# controlled_rectifier.net
KiCad netlist of a schematic drawn in Altium Designer
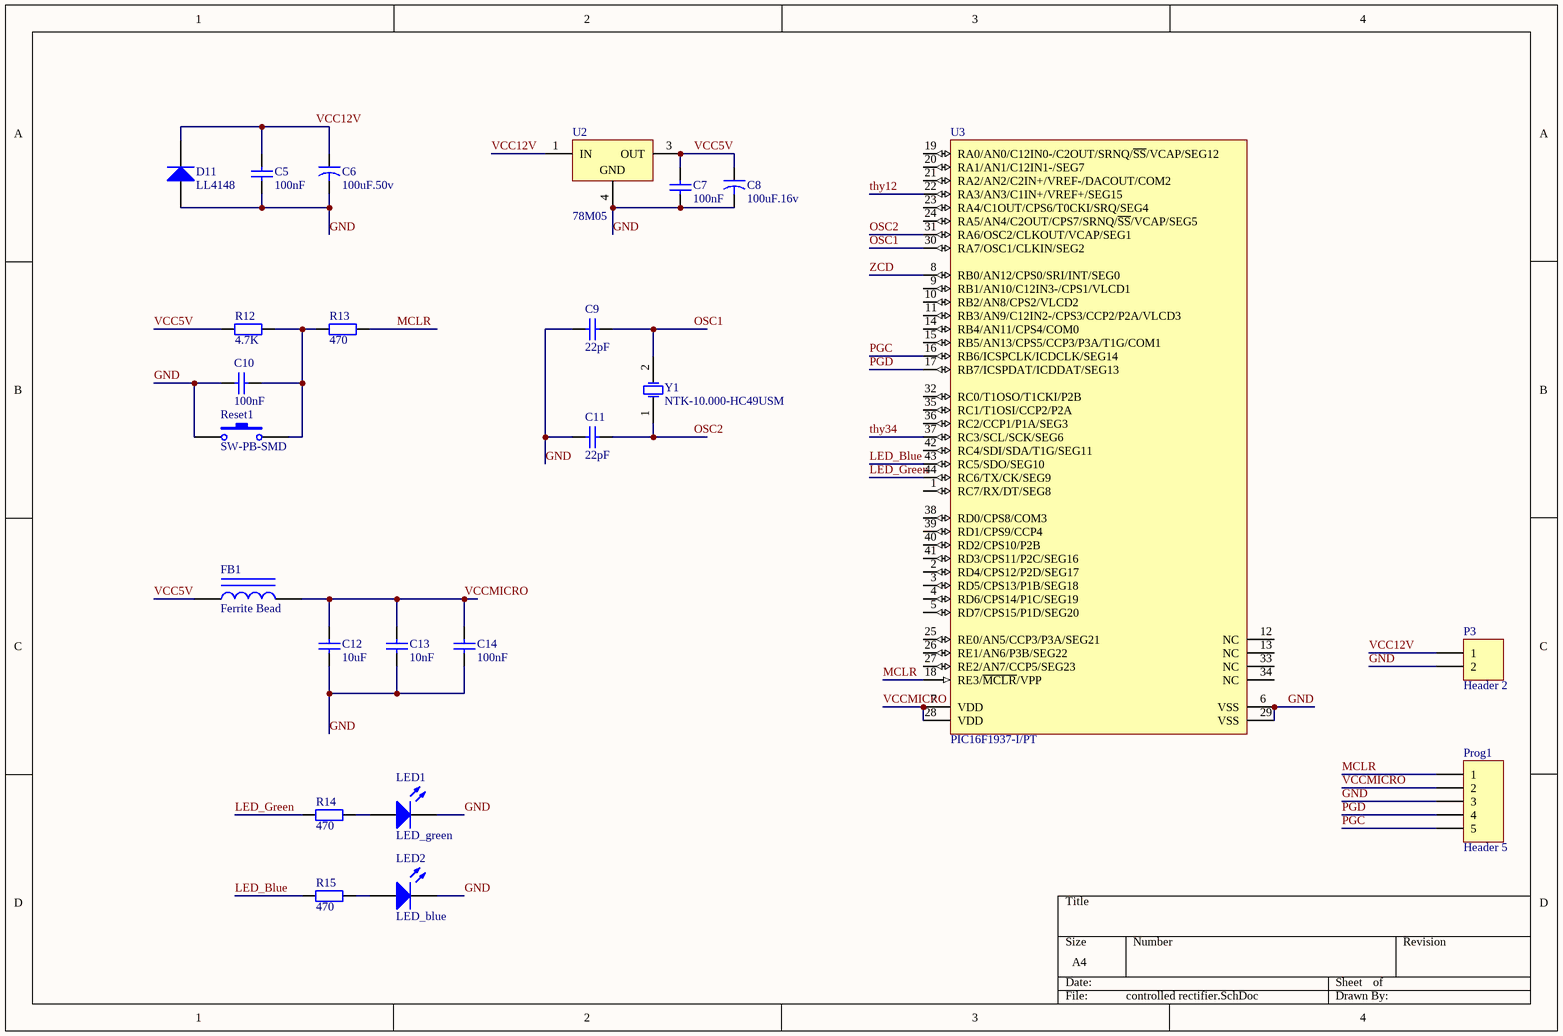
[diagram p0: controlled rectifier.SchDoc]

(export (version "E")
  (design (tool "Eeschema 10.0.6"))
  (components
    (comp (ref "C5")
      (value "100nF")
      (footprint "CAPS_0805")
      (description "CAP 0805")
      (fields (field (name "DESIGNER") "Abbas Basereh"))
      (libsource (lib "2016AbbasBasereh9365731239-12-10-95_-275613969") (part "CAP SMD 0805"))
    )
    (comp (ref "C6")
      (value "100uF.50v")
      (footprint "CAP_ELEC_SIZE_G")
      (description "Capacitor")
      (fields (field (name "PUBLISHER") "Altium Limited"))
      (libsource (lib "Miscellaneous Devices") (part "Cap2"))
    )
    (comp (ref "C7")
      (value "100nF")
      (footprint "CAPS_0805")
      (description "CAP 0805")
      (fields (field (name "DESIGNER") "Abbas Basereh"))
      (libsource (lib "2016AbbasBasereh9365731239-12-10-95_-275613969") (part "CAP SMD 0805"))
    )
    (comp (ref "C8")
      (value "100uF.16v")
      (footprint "CAP_ELEC_6.3x4.2")
      (description "Capacitor")
      (fields (field (name "PUBLISHER") "Altium Limited"))
      (libsource (lib "Miscellaneous Devices") (part "Cap2"))
    )
    (comp (ref "C9")
      (value "22pF")
      (footprint "CAPS_0805")
      (description "Capacitor")
      (fields (field (name "PUBLISHER") "Altium Limited"))
      (libsource (lib "DCMB_Economy_V00") (part "Cap"))
    )
    (comp (ref "C10")
      (value "100nF")
      (footprint "CAPS_0805")
      (description "Capacitor")
      (fields (field (name "PUBLISHER") "Altium Limited"))
      (libsource (lib "Miscellaneous Devices") (part "Cap"))
    )
    (comp (ref "C11")
      (value "22pF")
      (footprint "CAPS_0805")
      (description "Capacitor")
      (fields (field (name "PUBLISHER") "Altium Limited"))
      (libsource (lib "DCMB_Economy_V00") (part "Cap"))
    )
    (comp (ref "C12")
      (value "10uF")
      (footprint "CAPS_0805")
      (description "Capacitor")
      (fields (field (name "PUBLISHER") "Altium Limited"))
      (libsource (lib "DCMB_Economy_V00") (part "Cap"))
    )
    (comp (ref "C13")
      (value "10nF")
      (footprint "CAPS_0805")
      (description "Capacitor")
      (fields (field (name "PUBLISHER") "Altium Limited"))
      (libsource (lib "DCMB_Economy_V00") (part "Cap"))
    )
    (comp (ref "C14")
      (value "100nF")
      (footprint "CAPS_0805")
      (description "Capacitor")
      (fields (field (name "PUBLISHER") "Altium Limited"))
      (libsource (lib "DCMB_Economy_V00") (part "Cap"))
    )
    (comp (ref "D11")
      (value "LL4148")
      (footprint "SOD80, LL-34")
      (description "Default Diode")
      (fields (field (name "PUBLISHER") "Altium Limited"))
      (libsource (lib "Miscellaneous Devices") (part "Diode"))
    )
    (comp (ref "FB1")
      (value "Ferrite Bead")
      (footprint "FBC2012N")
      (description "Magnetic-Core Inductor")
      (fields (field (name "PUBLISHER") "Altium Limited"))
      (libsource (lib "Miscellaneous Devices") (part "Inductor Iron"))
    )
    (comp (ref "LED1")
      (value "LED_green")
      (footprint "LED-0805-A")
      (description "Typical RED, GREEN, YELLOW, AMBER GaAs LED")
      (fields (field (name "PUBLISHER") "Altium Limited"))
      (libsource (lib "Miscellaneous Devices") (part "LED2"))
    )
    (comp (ref "LED2")
      (value "LED_blue")
      (footprint "LED-0805-A")
      (description "Typical RED, GREEN, YELLOW, AMBER GaAs LED")
      (fields (field (name "PUBLISHER") "Altium Limited"))
      (libsource (lib "Miscellaneous Devices") (part "LED2"))
    )
    (comp (ref "P3")
      (value "Header 2")
      (footprint "Phoenix 2 Pin -RA")
      (description "Header, 2-Pin")
      (fields (field (name "PUBLISHER") "Altium Limited"))
      (libsource (lib "Miscellaneous Connectors") (part "Header 2"))
    )
    (comp (ref "Prog1")
      (value "Header 5")
      (footprint "SH-5 Pin")
      (description "Header, 5-Pin")
      (fields (field (name "PUBLISHER") "Altium Limited"))
      (libsource (lib "Miscellaneous Connectors") (part "Header 5"))
    )
    (comp (ref "R12")
      (value "4.7K")
      (footprint "RES_0805")
      (description "Resistor")
      (fields (field (name "PUBLISHER") "Altium Limited"))
      (libsource (lib "Miscellaneous Devices") (part "Res2"))
    )
    (comp (ref "R13")
      (value "470")
      (footprint "RES_0805")
      (description "Resistor")
      (fields (field (name "PUBLISHER") "Altium Limited"))
      (libsource (lib "Miscellaneous Devices") (part "Res2"))
    )
    (comp (ref "R14")
      (value "470")
      (footprint "RES_0805")
      (description "Resistor")
      (fields (field (name "PUBLISHER") "Altium Limited"))
      (libsource (lib "Miscellaneous Devices") (part "Res2"))
    )
    (comp (ref "R15")
      (value "470")
      (footprint "RES_0805")
      (description "Resistor")
      (fields (field (name "PUBLISHER") "Altium Limited"))
      (libsource (lib "Miscellaneous Devices") (part "Res2"))
    )
    (comp (ref "Reset1")
      (value "SW-PB-SMD")
      (footprint "KFC-6X6X4.5-4P-SMD")
      (description "Switch")
      (fields (field (name "PUBLISHER") "Altium Limited"))
      (libsource (lib "Miscellaneous Devices") (part "SW-PB"))
    )
    (comp (ref "U2")
      (value "78M05")
      (footprint "TO-252")
      (description "Positive-Voltage Regulator")
      (fields (field (name "PUBLISHER") "Altium Limited"))
      (libsource (lib "DCMB_Economy_V00") (part "µA78M05CKTPR"))
    )
    (comp (ref "U3")
      (value "PIC16F1937-I/PT")
      (footprint "TQFP-PT44_N")
      (fields (field (name "MANUFACTURER") "Microchip"))
      (libsource (lib "Microchip PIC16 Part 2") (part "PIC16F1937-I/PT"))
    )
    (comp (ref "Y1")
      (value "NTK-10.000-HC49USM")
      (footprint "XTLT_2")
      (description "Crystal Oscillator")
      (fields (field (name "PUBLISHER") "Altium Limited"))
      (libsource (lib "Miscellaneous Devices") (part "XTAL"))
    )
  )
  (nets
    (net (code "1") (name "/GND") (class "Default")
      (node (ref "C10") (pin "2") (pinfunction "2_2") (pintype "passive"))
      (node (ref "C11") (pin "1") (pinfunction "1_1") (pintype "passive"))
      (node (ref "C12") (pin "1") (pinfunction "1_1") (pintype "passive"))
      (node (ref "C13") (pin "1") (pinfunction "1_1") (pintype "passive"))
      (node (ref "C14") (pin "1") (pinfunction "1_1") (pintype "passive"))
      (node (ref "C5") (pin "1") (pinfunction "1_1") (pintype "passive"))
      (node (ref "C6") (pin "2") (pinfunction "2_2") (pintype "passive"))
      (node (ref "C7") (pin "1") (pinfunction "1_1") (pintype "passive"))
      (node (ref "C8") (pin "2") (pinfunction "2_2") (pintype "passive"))
      (node (ref "C9") (pin "1") (pinfunction "1_1") (pintype "passive"))
      (node (ref "D11") (pin "1") (pinfunction "A_1") (pintype "passive"))
      (node (ref "LED1") (pin "2") (pinfunction "K_2") (pintype "passive"))
      (node (ref "LED2") (pin "2") (pinfunction "K_2") (pintype "passive"))
      (node (ref "P3") (pin "2") (pinfunction "2_2") (pintype "passive"))
      (node (ref "Prog1") (pin "3") (pinfunction "3_3") (pintype "passive"))
      (node (ref "Reset1") (pin "1") (pinfunction "1_1") (pintype "passive"))
      (node (ref "U2") (pin "4") (pinfunction "GND_4") (pintype "power_in"))
      (node (ref "U3") (pin "29") (pinfunction "VSS_29") (pintype "power_in"))
      (node (ref "U3") (pin "6") (pinfunction "VSS_6") (pintype "power_in"))
    )
    (net (code "2") (name "/LED_Blue") (class "Default")
      (node (ref "R15") (pin "1") (pinfunction "1_1") (pintype "passive"))
      (node (ref "U3") (pin "43") (pinfunction "RC5/SDO/SEG10_43") (pintype "bidirectional"))
    )
    (net (code "3") (name "/LED_Green") (class "Default")
      (node (ref "R14") (pin "1") (pinfunction "1_1") (pintype "passive"))
      (node (ref "U3") (pin "44") (pinfunction "RC6/TX/CK/SEG9_44") (pintype "bidirectional"))
    )
    (net (code "4") (name "/MCLR") (class "Default")
      (node (ref "Prog1") (pin "1") (pinfunction "1_1") (pintype "passive"))
      (node (ref "R13") (pin "2") (pinfunction "2_2") (pintype "passive"))
      (node (ref "U3") (pin "18") (pinfunction "RE3/~{MCLR}/VPP_18") (pintype "input"))
    )
    (net (code "5") (name "/OSC1") (class "Default")
      (node (ref "C9") (pin "2") (pinfunction "2_2") (pintype "passive"))
      (node (ref "U3") (pin "30") (pinfunction "RA7/OSC1/CLKIN/SEG2_30") (pintype "bidirectional"))
      (node (ref "Y1") (pin "2") (pinfunction "OSC2_2") (pintype "passive"))
    )
    (net (code "6") (name "/OSC2") (class "Default")
      (node (ref "C11") (pin "2") (pinfunction "2_2") (pintype "passive"))
      (node (ref "U3") (pin "31") (pinfunction "RA6/OSC2/CLKOUT/VCAP/SEG1_31") (pintype "bidirectional"))
      (node (ref "Y1") (pin "1") (pinfunction "OSC1_1") (pintype "passive"))
    )
    (net (code "7") (name "/PGC") (class "Default")
      (node (ref "Prog1") (pin "5") (pinfunction "5_5") (pintype "passive"))
      (node (ref "U3") (pin "16") (pinfunction "RB6/ICSPCLK/ICDCLK/SEG14_16") (pintype "bidirectional"))
    )
    (net (code "8") (name "/PGD") (class "Default")
      (node (ref "Prog1") (pin "4") (pinfunction "4_4") (pintype "passive"))
      (node (ref "U3") (pin "17") (pinfunction "RB7/ICSPDAT/ICDDAT/SEG13_17") (pintype "bidirectional"))
    )
    (net (code "9") (name "/VCC5V") (class "Default")
      (node (ref "C7") (pin "2") (pinfunction "2_2") (pintype "passive"))
      (node (ref "C8") (pin "1") (pinfunction "1_1") (pintype "passive"))
      (node (ref "FB1") (pin "1") (pinfunction "1_1") (pintype "passive"))
      (node (ref "R12") (pin "1") (pinfunction "1_1") (pintype "passive"))
      (node (ref "U2") (pin "3") (pinfunction "OUT_3") (pintype "power_in"))
    )
    (net (code "10") (name "/VCC12V") (class "Default")
      (node (ref "C5") (pin "2") (pinfunction "2_2") (pintype "passive"))
      (node (ref "C6") (pin "1") (pinfunction "1_1") (pintype "passive"))
      (node (ref "D11") (pin "2") (pinfunction "K_2") (pintype "passive"))
      (node (ref "P3") (pin "1") (pinfunction "1_1") (pintype "passive"))
      (node (ref "U2") (pin "1") (pinfunction "IN_1") (pintype "power_in"))
    )
    (net (code "11") (name "/VCCMICRO") (class "Default")
      (node (ref "C12") (pin "2") (pinfunction "2_2") (pintype "passive"))
      (node (ref "C13") (pin "2") (pinfunction "2_2") (pintype "passive"))
      (node (ref "C14") (pin "2") (pinfunction "2_2") (pintype "passive"))
      (node (ref "FB1") (pin "2") (pinfunction "2_2") (pintype "passive"))
      (node (ref "Prog1") (pin "2") (pinfunction "2_2") (pintype "passive"))
      (node (ref "U3") (pin "28") (pinfunction "VDD_28") (pintype "power_in"))
      (node (ref "U3") (pin "7") (pinfunction "VDD_7") (pintype "power_in"))
    )
    (net (code "12") (name "/ZCD") (class "Default")
      (node (ref "U3") (pin "8") (pinfunction "RB0/AN12/CPS0/SRI/INT/SEG0_8") (pintype "bidirectional"))
    )
    (net (code "13") (name "/thy12") (class "Default")
      (node (ref "U3") (pin "22") (pinfunction "RA3/AN3/C1IN+/VREF+/SEG15_22") (pintype "bidirectional"))
    )
    (net (code "14") (name "/thy34") (class "Default")
      (node (ref "U3") (pin "37") (pinfunction "RC3/SCL/SCK/SEG6_37") (pintype "bidirectional"))
    )
    (net (code "15") (name "Net-(C10-Pad1)") (class "Default")
      (node (ref "C10") (pin "1") (pinfunction "1_1") (pintype "passive"))
      (node (ref "R12") (pin "2") (pinfunction "2_2") (pintype "passive"))
      (node (ref "R13") (pin "1") (pinfunction "1_1") (pintype "passive"))
      (node (ref "Reset1") (pin "2") (pinfunction "2_2") (pintype "passive"))
    )
    (net (code "16") (name "Net-(LED1-A)") (class "Default")
      (node (ref "LED1") (pin "1") (pinfunction "A_1") (pintype "passive"))
      (node (ref "R14") (pin "2") (pinfunction "2_2") (pintype "passive"))
    )
    (net (code "17") (name "Net-(LED2-A)") (class "Default")
      (node (ref "LED2") (pin "1") (pinfunction "A_1") (pintype "passive"))
      (node (ref "R15") (pin "2") (pinfunction "2_2") (pintype "passive"))
    )
    (net (code "18") (name "unconnected-(U3-NC-Pad12)") (class "Default")
      (node (ref "U3") (pin "12") (pinfunction "NC_12") (pintype "passive"))
    )
    (net (code "19") (name "unconnected-(U3-NC-Pad13)") (class "Default")
      (node (ref "U3") (pin "13") (pinfunction "NC_13") (pintype "passive"))
    )
    (net (code "20") (name "unconnected-(U3-NC-Pad33)") (class "Default")
      (node (ref "U3") (pin "33") (pinfunction "NC_33") (pintype "passive"))
    )
    (net (code "21") (name "unconnected-(U3-NC-Pad34)") (class "Default")
      (node (ref "U3") (pin "34") (pinfunction "NC_34") (pintype "passive"))
    )
    (net (code "22") (name "unconnected-(U3-RA0{slash}AN0{slash}C12IN0-{slash}C2OUT{slash}SRNQ{slash}~{SS}{slash}VCAP{slash}SEG12-Pad19)") (class "Default")
      (node (ref "U3") (pin "19") (pinfunction "RA0/AN0/C12IN0-/C2OUT/SRNQ/~{SS}/VCAP/SEG12_19") (pintype "bidirectional"))
    )
    (net (code "23") (name "unconnected-(U3-RA1{slash}AN1{slash}C12IN1-{slash}SEG7-Pad20)") (class "Default")
      (node (ref "U3") (pin "20") (pinfunction "RA1/AN1/C12IN1-/SEG7_20") (pintype "bidirectional"))
    )
    (net (code "24") (name "unconnected-(U3-RA2{slash}AN2{slash}C2IN+{slash}VREF-{slash}DACOUT{slash}COM2-Pad21)") (class "Default")
      (node (ref "U3") (pin "21") (pinfunction "RA2/AN2/C2IN+/VREF-/DACOUT/COM2_21") (pintype "bidirectional"))
    )
    (net (code "25") (name "unconnected-(U3-RA4{slash}C1OUT{slash}CPS6{slash}T0CKI{slash}SRQ{slash}SEG4-Pad23)") (class "Default")
      (node (ref "U3") (pin "23") (pinfunction "RA4/C1OUT/CPS6/T0CKI/SRQ/SEG4_23") (pintype "bidirectional"))
    )
    (net (code "26") (name "unconnected-(U3-RA5{slash}AN4{slash}C2OUT{slash}CPS7{slash}SRNQ{slash}~{SS}{slash}VCAP{slash}SEG5-Pad24)") (class "Default")
      (node (ref "U3") (pin "24") (pinfunction "RA5/AN4/C2OUT/CPS7/SRNQ/~{SS}/VCAP/SEG5_24") (pintype "bidirectional"))
    )
    (net (code "27") (name "unconnected-(U3-RB1{slash}AN10{slash}C12IN3-{slash}CPS1{slash}VLCD1-Pad9)") (class "Default")
      (node (ref "U3") (pin "9") (pinfunction "RB1/AN10/C12IN3-/CPS1/VLCD1_9") (pintype "bidirectional"))
    )
    (net (code "28") (name "unconnected-(U3-RB2{slash}AN8{slash}CPS2{slash}VLCD2-Pad10)") (class "Default")
      (node (ref "U3") (pin "10") (pinfunction "RB2/AN8/CPS2/VLCD2_10") (pintype "bidirectional"))
    )
    (net (code "29") (name "unconnected-(U3-RB3{slash}AN9{slash}C12IN2-{slash}CPS3{slash}CCP2{slash}P2A{slash}VLCD3-Pad11)") (class "Default")
      (node (ref "U3") (pin "11") (pinfunction "RB3/AN9/C12IN2-/CPS3/CCP2/P2A/VLCD3_11") (pintype "bidirectional"))
    )
    (net (code "30") (name "unconnected-(U3-RB4{slash}AN11{slash}CPS4{slash}COM0-Pad14)") (class "Default")
      (node (ref "U3") (pin "14") (pinfunction "RB4/AN11/CPS4/COM0_14") (pintype "bidirectional"))
    )
    (net (code "31") (name "unconnected-(U3-RB5{slash}AN13{slash}CPS5{slash}CCP3{slash}P3A{slash}T1G{slash}COM1-Pad15)") (class "Default")
      (node (ref "U3") (pin "15") (pinfunction "RB5/AN13/CPS5/CCP3/P3A/T1G/COM1_15") (pintype "bidirectional"))
    )
    (net (code "32") (name "unconnected-(U3-RC0{slash}T1OSO{slash}T1CKI{slash}P2B-Pad32)") (class "Default")
      (node (ref "U3") (pin "32") (pinfunction "RC0/T1OSO/T1CKI/P2B_32") (pintype "bidirectional"))
    )
    (net (code "33") (name "unconnected-(U3-RC1{slash}T1OSI{slash}CCP2{slash}P2A-Pad35)") (class "Default")
      (node (ref "U3") (pin "35") (pinfunction "RC1/T1OSI/CCP2/P2A_35") (pintype "bidirectional"))
    )
    (net (code "34") (name "unconnected-(U3-RC2{slash}CCP1{slash}P1A{slash}SEG3-Pad36)") (class "Default")
      (node (ref "U3") (pin "36") (pinfunction "RC2/CCP1/P1A/SEG3_36") (pintype "bidirectional"))
    )
    (net (code "35") (name "unconnected-(U3-RC4{slash}SDI{slash}SDA{slash}T1G{slash}SEG11-Pad42)") (class "Default")
      (node (ref "U3") (pin "42") (pinfunction "RC4/SDI/SDA/T1G/SEG11_42") (pintype "bidirectional"))
    )
    (net (code "36") (name "unconnected-(U3-RC7{slash}RX{slash}DT{slash}SEG8-Pad1)") (class "Default")
      (node (ref "U3") (pin "1") (pinfunction "RC7/RX/DT/SEG8_1") (pintype "bidirectional"))
    )
    (net (code "37") (name "unconnected-(U3-RD0{slash}CPS8{slash}COM3-Pad38)") (class "Default")
      (node (ref "U3") (pin "38") (pinfunction "RD0/CPS8/COM3_38") (pintype "bidirectional"))
    )
    (net (code "38") (name "unconnected-(U3-RD1{slash}CPS9{slash}CCP4-Pad39)") (class "Default")
      (node (ref "U3") (pin "39") (pinfunction "RD1/CPS9/CCP4_39") (pintype "bidirectional"))
    )
    (net (code "39") (name "unconnected-(U3-RD2{slash}CPS10{slash}P2B-Pad40)") (class "Default")
      (node (ref "U3") (pin "40") (pinfunction "RD2/CPS10/P2B_40") (pintype "bidirectional"))
    )
    (net (code "40") (name "unconnected-(U3-RD3{slash}CPS11{slash}P2C{slash}SEG16-Pad41)") (class "Default")
      (node (ref "U3") (pin "41") (pinfunction "RD3/CPS11/P2C/SEG16_41") (pintype "bidirectional"))
    )
    (net (code "41") (name "unconnected-(U3-RD4{slash}CPS12{slash}P2D{slash}SEG17-Pad2)") (class "Default")
      (node (ref "U3") (pin "2") (pinfunction "RD4/CPS12/P2D/SEG17_2") (pintype "bidirectional"))
    )
    (net (code "42") (name "unconnected-(U3-RD5{slash}CPS13{slash}P1B{slash}SEG18-Pad3)") (class "Default")
      (node (ref "U3") (pin "3") (pinfunction "RD5/CPS13/P1B/SEG18_3") (pintype "bidirectional"))
    )
    (net (code "43") (name "unconnected-(U3-RD6{slash}CPS14{slash}P1C{slash}SEG19-Pad4)") (class "Default")
      (node (ref "U3") (pin "4") (pinfunction "RD6/CPS14/P1C/SEG19_4") (pintype "bidirectional"))
    )
    (net (code "44") (name "unconnected-(U3-RD7{slash}CPS15{slash}P1D{slash}SEG20-Pad5)") (class "Default")
      (node (ref "U3") (pin "5") (pinfunction "RD7/CPS15/P1D/SEG20_5") (pintype "bidirectional"))
    )
    (net (code "45") (name "unconnected-(U3-RE0{slash}AN5{slash}CCP3{slash}P3A{slash}SEG21-Pad25)") (class "Default")
      (node (ref "U3") (pin "25") (pinfunction "RE0/AN5/CCP3/P3A/SEG21_25") (pintype "bidirectional"))
    )
    (net (code "46") (name "unconnected-(U3-RE1{slash}AN6{slash}P3B{slash}SEG22-Pad26)") (class "Default")
      (node (ref "U3") (pin "26") (pinfunction "RE1/AN6/P3B/SEG22_26") (pintype "bidirectional"))
    )
    (net (code "47") (name "unconnected-(U3-RE2{slash}AN7{slash}CCP5{slash}SEG23-Pad27)") (class "Default")
      (node (ref "U3") (pin "27") (pinfunction "RE2/AN7/CCP5/SEG23_27") (pintype "bidirectional"))
    )
  )
)
